# Power.net
KiCad netlist of a schematic drawn in Altium Designer
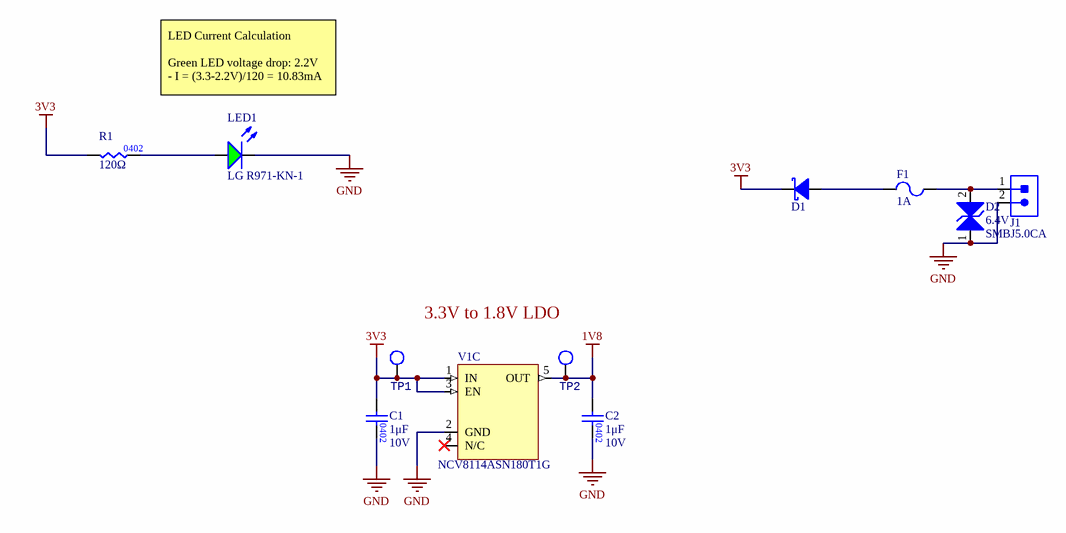
[diagram p0: Power.SchDoc]

(export (version "E")
  (design (tool "Eeschema 10.0.6"))
  (components
    (comp (ref "C1")
      (value "CAP_1UF_10V_0402_X5R")
      (footprint "CAP0402")
      (description "CAP CER 1UF 10V X5R 0402")
      (fields
        (field (name "MANUFACTURER") "Kyocera AVX")
        (field (name "MANUFACTURER PART NUMBER") "0402ZD105MAT2A")
        (field (name "CAPACITANCE") "1μF")
        (field (name "RATED DC VOLTAGE (URDC)") "10V")
      )
      (libsource (lib "UWRT_Schematic_Library_2020") (part "CAP_1UF_10V_0402_X5R"))
    )
    (comp (ref "C2")
      (value "CAP_1UF_10V_0402_X5R")
      (footprint "CAP0402")
      (description "CAP CER 1UF 10V X5R 0402")
      (fields
        (field (name "MANUFACTURER") "Kyocera AVX")
        (field (name "MANUFACTURER PART NUMBER") "0402ZD105MAT2A")
        (field (name "CAPACITANCE") "1μF")
        (field (name "RATED DC VOLTAGE (URDC)") "10V")
      )
      (libsource (lib "UWRT_Schematic_Library_2020") (part "CAP_1UF_10V_0402_X5R"))
    )
    (comp (ref "D1")
      (value "DIO_SCHOTTKY_30V_800mA")
      (footprint "SOD-323_UNIDIR")
      (description "DIODE SCHOTTKY 30V 800MA USC")
      (libsource (lib "UWRT_Schematic_Library_2020") (part "DIO_SCHOTTKY_30V_800mA"))
    )
    (comp (ref "D2")
      (value "TVS_DIODE_BIDIR_5V")
      (footprint "TVS_DIODE_BIDIR_SMB")
      (description "TVS DIODE 5V 9.2V SMB")
      (fields
        (field (name "VOLTAGE - BREAKDOWN (MIN)") "6.4V")
        (field (name "MANUFACTURER PART NUMBER 1") "SMBJ5.0CA")
      )
      (libsource (lib "UWRT_Schematic_Library_2020") (part "TVS_DIODE_BIDIR_5V"))
    )
    (comp (ref "F1")
      (value "FUSE_1A_1206")
      (footprint "FUSE_1206")
      (description "FUSE BOARD MOUNT 1A 125VAC 63VDC")
      (fields (field (name "CURRENT RATING") "1A"))
      (libsource (lib "UWRT_Schematic_Library_2020") (part "FUSE_1A_1206"))
    )
    (comp (ref "J1")
      (value "CON_2POS_SCREW_TERM")
      (footprint "1935161")
      (description "TERM BLK 2POS SIDE ENTRY 5MM")
      (libsource (lib "UWRT_Schematic_Library_2020") (part "CON_2POS_SCREW_TERM"))
    )
    (comp (ref "LED1")
      (value "LED_GREEN")
      (footprint "LED_0805_GREEN")
      (description "LED GREEN DIFFUSED 0805 SMD")
      (fields (field (name "MANUFACTURER PART NUMBER 1") "LG R971-KN-1"))
      (libsource (lib "UWRT_Schematic_Library_2020") (part "LED_GREEN"))
    )
    (comp (ref "R1")
      (value "120Ω")
      (footprint "RES0402")
      (description "RES 120 OHM 5% 1/16W 0402")
      (fields (field (name "POWER") "1/16W") (field (name "TOLERANCE") "5%"))
      (libsource (lib "UWRT_Schematic_Library_2020") (part "RES_120Ω_0402_5%"))
    )
    (comp (ref "TP1")
      (value "TESTPOINT_LOOP")
      (footprint "TESTPOINT_LOOP")
      (description "TESTPOINT THRUHOLE")
      (libsource (lib "UWRT_Schematic_Library_2020") (part "TESTPOINT_LOOP"))
    )
    (comp (ref "TP2")
      (value "TESTPOINT_LOOP")
      (footprint "TESTPOINT_LOOP")
      (description "TESTPOINT THRUHOLE")
      (libsource (lib "UWRT_Schematic_Library_2020") (part "TESTPOINT_LOOP"))
    )
    (comp (ref "V1")
      (value "NCV8114ASN180T1G")
      (footprint "1.8V_Output_LDO")
      (description "Linear Voltage Regulator IC Positive Fixed 1 Output 300mA 5-TSOP")
      (libsource (lib "UWRT_Schematic_Library_2020") (part "1.8V_Output_LDO"))
    )
  )
  (nets
    (net (code "1") (name "1V8") (class "Default")
      (node (ref "C2") (pin "1") (pinfunction "1_1") (pintype "passive"))
      (node (ref "TP2") (pin "1") (pintype "passive"))
      (node (ref "V1") (pin "5") (pinfunction "OUT_5") (pintype "output"))
    )
    (net (code "2") (name "3V3") (class "Default")
      (node (ref "C1") (pin "1") (pinfunction "1_1") (pintype "passive"))
      (node (ref "D1") (pin "2") (pinfunction "Cathode_2") (pintype "passive"))
      (node (ref "R1") (pin "1") (pinfunction "1_1") (pintype "passive"))
      (node (ref "TP1") (pin "1") (pintype "passive"))
      (node (ref "V1") (pin "1") (pinfunction "IN_1") (pintype "input"))
      (node (ref "V1") (pin "3") (pinfunction "EN_3") (pintype "input"))
    )
    (net (code "3") (name "GND") (class "Default")
      (node (ref "C1") (pin "2") (pinfunction "2_2") (pintype "passive"))
      (node (ref "C2") (pin "2") (pinfunction "2_2") (pintype "passive"))
      (node (ref "D2") (pin "1") (pinfunction "1_1") (pintype "passive"))
      (node (ref "J1") (pin "2") (pinfunction "2_2") (pintype "passive"))
      (node (ref "LED1") (pin "2") (pinfunction "K_2") (pintype "passive"))
      (node (ref "V1") (pin "2") (pinfunction "GND_2") (pintype "passive"))
    )
    (net (code "4") (name "Net-(D1-Anode)") (class "Default")
      (node (ref "D1") (pin "1") (pinfunction "Anode_1") (pintype "passive"))
      (node (ref "F1") (pin "1") (pinfunction "1_1") (pintype "passive"))
    )
    (net (code "5") (name "Net-(D2-Pad2)") (class "Default")
      (node (ref "D2") (pin "2") (pinfunction "2_2") (pintype "passive"))
      (node (ref "F1") (pin "2") (pinfunction "2_2") (pintype "passive"))
      (node (ref "J1") (pin "1") (pinfunction "1_1") (pintype "passive"))
    )
    (net (code "6") (name "Net-(LED1-A)") (class "Default")
      (node (ref "LED1") (pin "1") (pinfunction "A_1") (pintype "passive"))
      (node (ref "R1") (pin "2") (pinfunction "2_2") (pintype "passive"))
    )
    (net (code "7") (name "unconnected-(V1C-N{slash}C-Pad4)") (class "Default")
      (node (ref "V1") (pin "4") (pinfunction "N/C_4") (pintype "passive+no_connect"))
    )
  )
)
